# Group_04.net
KiCad netlist of a schematic drawn in EAGLE
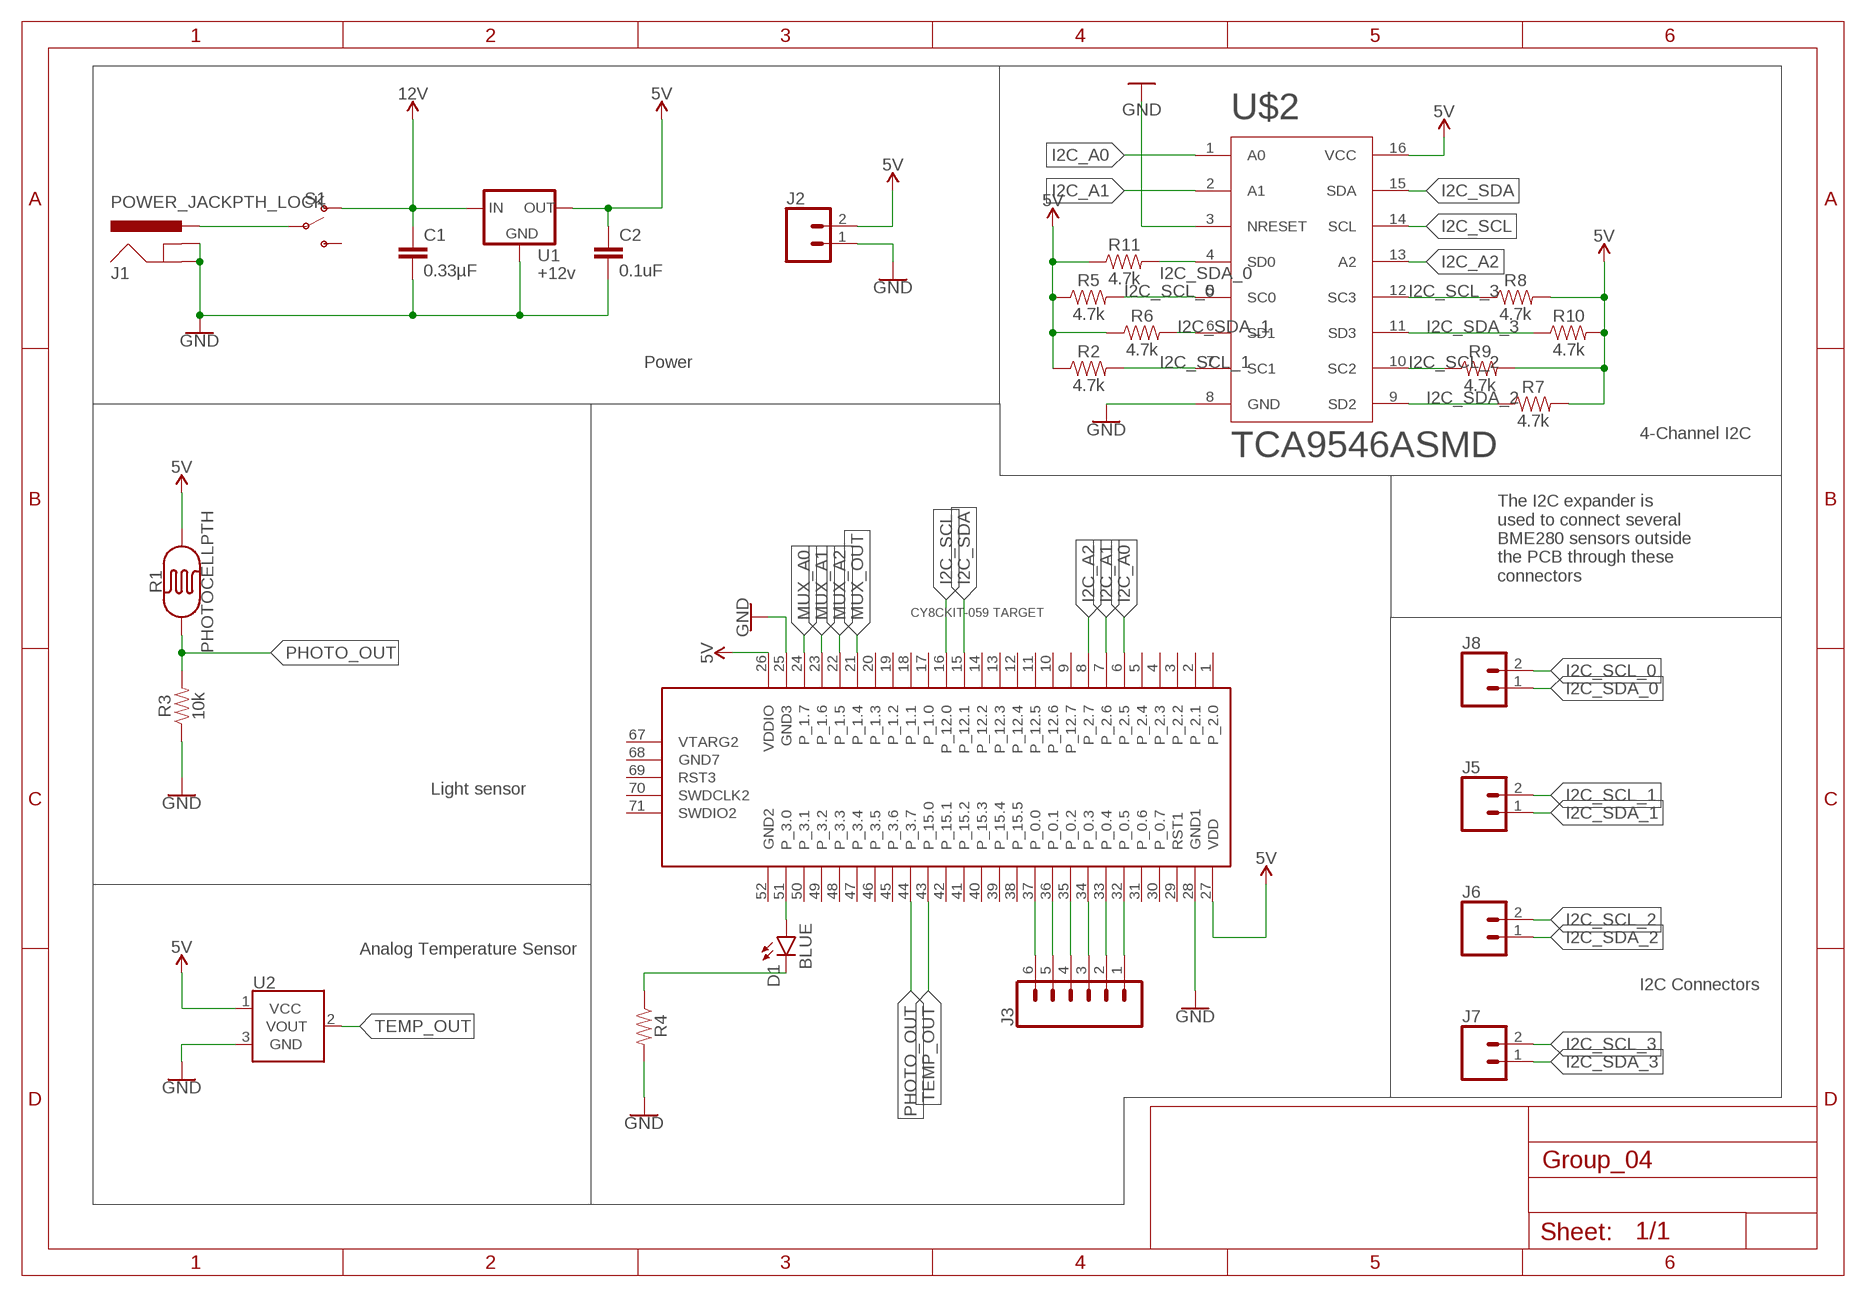
[diagram p0: schematic, sheet 1, part 1 of 2]
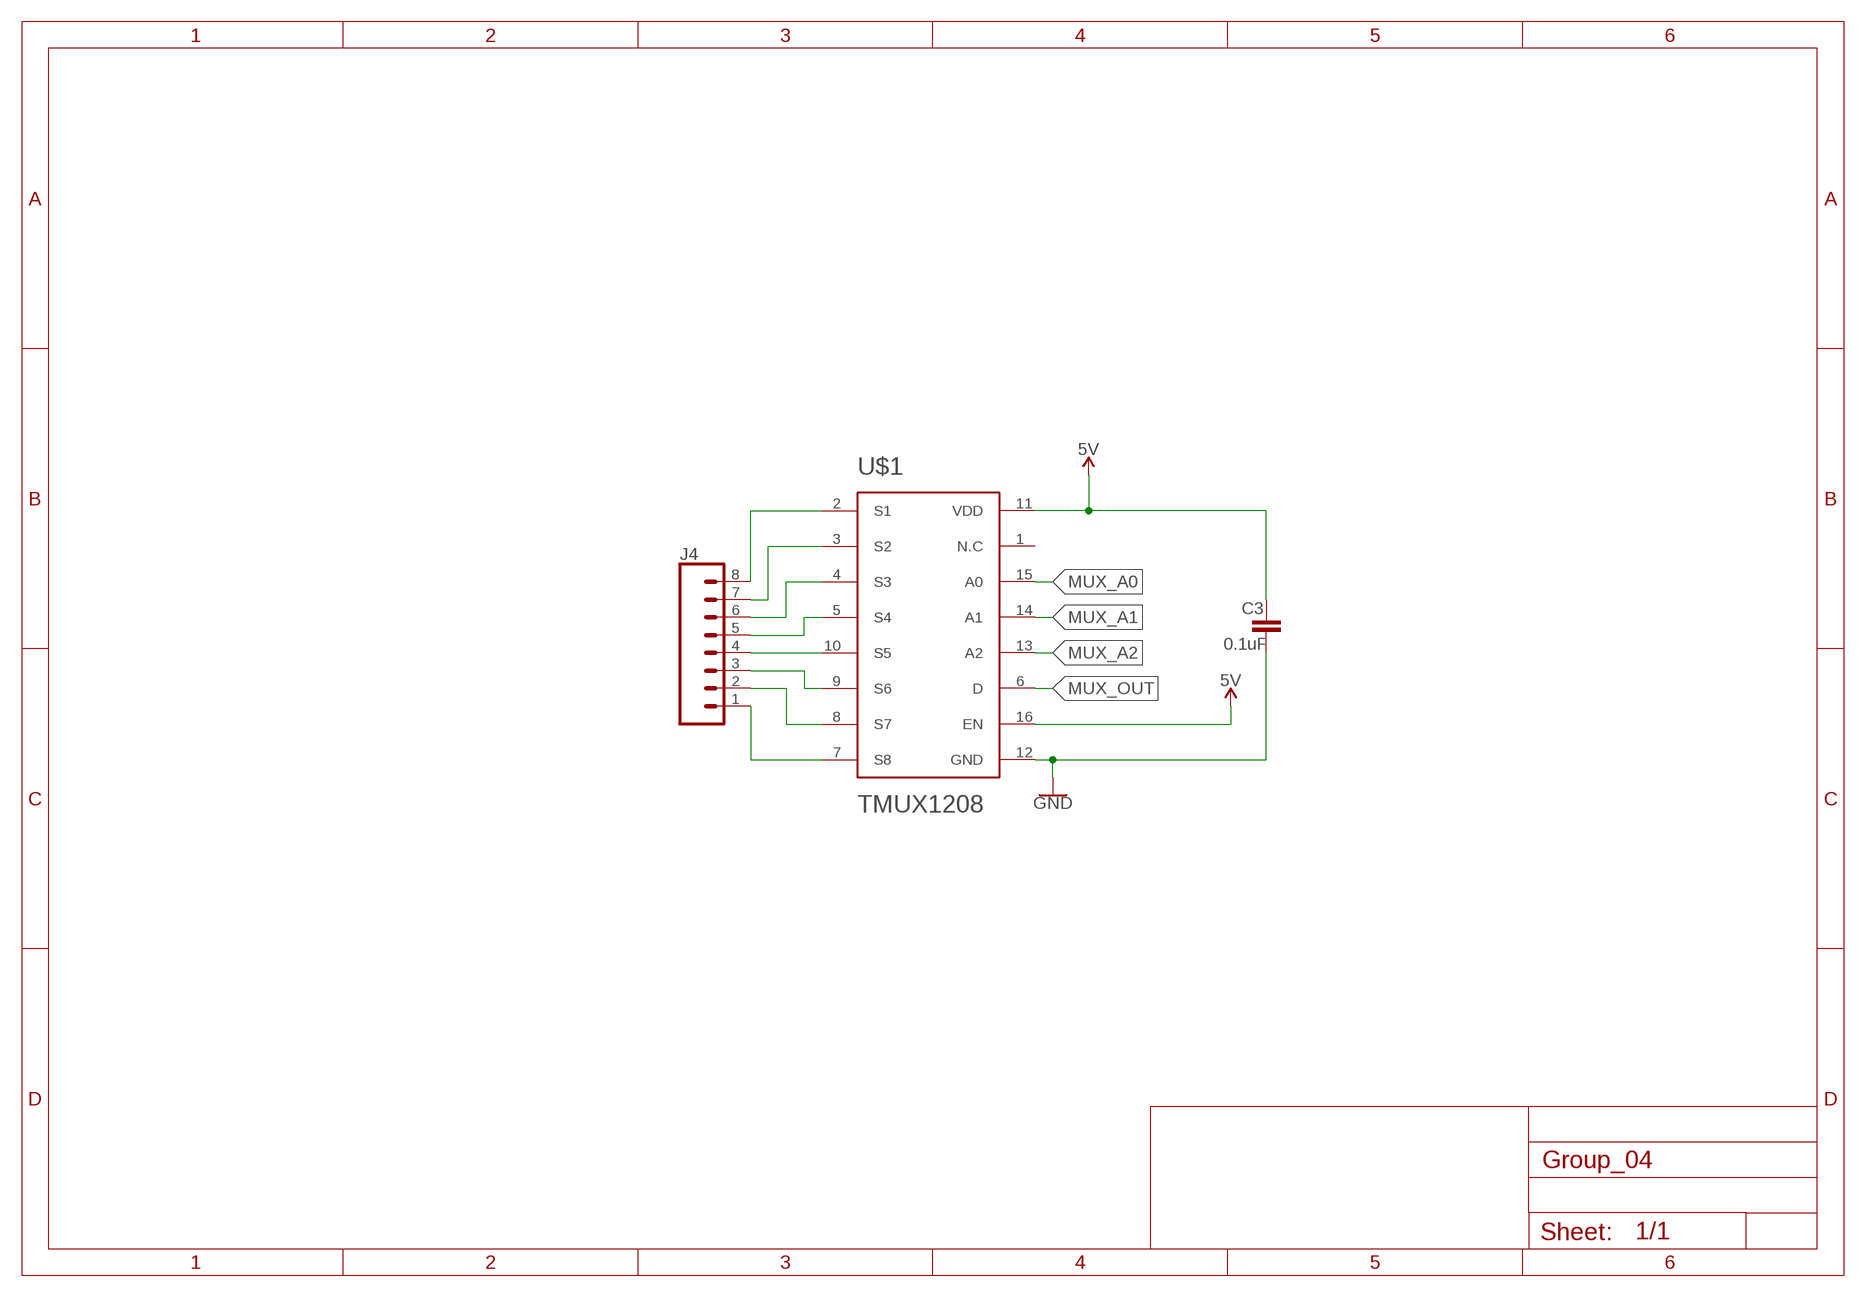
[diagram p1: schematic, sheet 1, part 2 of 2]

(export (version "E")
  (design (tool "Eeschema 10.0.6"))
  (components
    (comp (ref "C1")
      (value "0.33µF")
      (footprint "eagle-import:0805")
      (libsource (lib "eagle-import") (part "0.33UF/330NF-0805-50V-10%"))
    )
    (comp (ref "C2")
      (value "0.1uF")
      (footprint "eagle-import:CAP-PTH-SMALL-KIT")
      (libsource (lib "eagle-import") (part "0.1UF-KIT-EZ-50V-20%"))
    )
    (comp (ref "C3")
      (value "0.1uF")
      (footprint "eagle-import:CAP-PTH-SMALL-KIT")
      (libsource (lib "eagle-import") (part "0.1UF-KIT-EZ-50V-20%"))
    )
    (comp (ref "D1")
      (value "BLUE")
      (footprint "eagle-import:LED-1206")
      (libsource (lib "eagle-import") (part "LED-BLUE1206"))
    )
    (comp (ref "J1")
      (value "POWER_JACKPTH_LOCK")
      (footprint "eagle-import:POWER_JACK_PTH_LOCK")
      (libsource (lib "eagle-import") (part "POWER_JACKPTH_LOCK"))
    )
    (comp (ref "J2")
      (value "CONN_02")
      (footprint "eagle-import:1X02")
      (libsource (lib "eagle-import") (part "CONN_02"))
    )
    (comp (ref "J3")
      (value "CONN_06LOCK")
      (footprint "eagle-import:1X06_LOCK")
      (libsource (lib "eagle-import") (part "CONN_06LOCK"))
    )
    (comp (ref "J4")
      (value "CONN_08LOCK")
      (footprint "eagle-import:1X08_LOCK")
      (libsource (lib "eagle-import") (part "CONN_08LOCK"))
    )
    (comp (ref "J5")
      (value "CONN_02")
      (footprint "eagle-import:1X02")
      (libsource (lib "eagle-import") (part "CONN_02"))
    )
    (comp (ref "J6")
      (value "CONN_02")
      (footprint "eagle-import:1X02")
      (libsource (lib "eagle-import") (part "CONN_02"))
    )
    (comp (ref "J7")
      (value "CONN_02")
      (footprint "eagle-import:1X02")
      (libsource (lib "eagle-import") (part "CONN_02"))
    )
    (comp (ref "J8")
      (value "CONN_02")
      (footprint "eagle-import:1X02")
      (libsource (lib "eagle-import") (part "CONN_02"))
    )
    (comp (ref "R1")
      (value "PHOTOCELLPTH")
      (footprint "eagle-import:PHOTOCELL")
      (libsource (lib "eagle-import") (part "PHOTOCELLPTH"))
    )
    (comp (ref "R2")
      (value "4.7k")
      (footprint "eagle-import:0603")
      (libsource (lib "eagle-import") (part "4.7KOHM-0603-1/10W-1%"))
    )
    (comp (ref "R3")
      (value "10k")
      (footprint "eagle-import:0603")
      (libsource (lib "eagle-import") (part "10KOHM-0603-1/10W-1%"))
    )
    (comp (ref "R4")
      (value "RESISTORAXIAL-0.3")
      (footprint "eagle-import:AXIAL-0.3")
      (libsource (lib "eagle-import") (part "RESISTORAXIAL-0.3"))
    )
    (comp (ref "R5")
      (value "4.7k")
      (footprint "eagle-import:0603")
      (libsource (lib "eagle-import") (part "4.7KOHM-0603-1/10W-1%"))
    )
    (comp (ref "R6")
      (value "4.7k")
      (footprint "eagle-import:0603")
      (libsource (lib "eagle-import") (part "4.7KOHM-0603-1/10W-1%"))
    )
    (comp (ref "R7")
      (value "4.7k")
      (footprint "eagle-import:0603")
      (libsource (lib "eagle-import") (part "4.7KOHM-0603-1/10W-1%"))
    )
    (comp (ref "R8")
      (value "4.7k")
      (footprint "eagle-import:0603")
      (libsource (lib "eagle-import") (part "4.7KOHM-0603-1/10W-1%"))
    )
    (comp (ref "R9")
      (value "4.7k")
      (footprint "eagle-import:0603")
      (libsource (lib "eagle-import") (part "4.7KOHM-0603-1/10W-1%"))
    )
    (comp (ref "R10")
      (value "4.7k")
      (footprint "eagle-import:0603")
      (libsource (lib "eagle-import") (part "4.7KOHM-0603-1/10W-1%"))
    )
    (comp (ref "R11")
      (value "4.7k")
      (footprint "eagle-import:0603")
      (libsource (lib "eagle-import") (part "4.7KOHM-0603-1/10W-1%"))
    )
    (comp (ref "S1")
      (value "SWITCH-SPDT-PTH-11.6X4.0MM")
      (footprint "eagle-import:SWITCH_SPDT_PTH_11.6X4.0MM")
      (libsource (lib "eagle-import") (part "SWITCH-SPDT-PTH-11.6X4.0MM"))
    )
    (comp (ref "U$1")
      (value "TMUX1208")
      (footprint "eagle-import:QFN-16")
      (libsource (lib "eagle-import") (part "TMUX1208"))
    )
    (comp (ref "U$2")
      (value "TCA9546ASMD")
      (footprint "eagle-import:TSSOP-16")
      (libsource (lib "eagle-import") (part "TCA9546ASMD"))
    )
    (comp (ref "U$3")
      (value "CY8CKIT-059_TARGET")
      (footprint "eagle-import:CY8CKIT-059_TARGET")
      (libsource (lib "eagle-import") (part "CY8CKIT-059_TARGET"))
    )
    (comp (ref "U1")
      (value "+12v")
      (footprint "eagle-import:TO-252")
      (libsource (lib "eagle-import") (part "V_REG_78XX7812"))
    )
    (comp (ref "U2")
      (value "TMP36GT9")
      (footprint "eagle-import:TO-92")
      (libsource (lib "eagle-import") (part "TMP36GT9"))
    )
  )
  (nets
    (net (code "1") (name "5V") (class "Default")
      (node (ref "C2") (pin "1") (pinfunction "1_1") (pintype "passive"))
      (node (ref "C3") (pin "1") (pinfunction "1_1") (pintype "passive"))
      (node (ref "J2") (pin "2") (pinfunction "2_2") (pintype "passive"))
      (node (ref "R1") (pin "2") (pinfunction "P$2_2") (pintype "bidirectional"))
      (node (ref "R10") (pin "2") (pinfunction "2_2") (pintype "passive"))
      (node (ref "R11") (pin "1") (pinfunction "1_1") (pintype "passive"))
      (node (ref "R2") (pin "1") (pinfunction "1_1") (pintype "passive"))
      (node (ref "R5") (pin "1") (pinfunction "1_1") (pintype "passive"))
      (node (ref "R6") (pin "1") (pinfunction "1_1") (pintype "passive"))
      (node (ref "R7") (pin "2") (pinfunction "2_2") (pintype "passive"))
      (node (ref "R8") (pin "2") (pinfunction "2_2") (pintype "passive"))
      (node (ref "R9") (pin "2") (pinfunction "2_2") (pintype "passive"))
      (node (ref "U$1") (pin "11") (pinfunction "VDD_11") (pintype "bidirectional"))
      (node (ref "U$1") (pin "16") (pinfunction "EN_16") (pintype "bidirectional"))
      (node (ref "U$2") (pin "16") (pinfunction "VCC_16") (pintype "bidirectional"))
      (node (ref "U$3") (pin "26") (pinfunction "VDDIO_26") (pintype "bidirectional"))
      (node (ref "U$3") (pin "27") (pinfunction "VDD_27") (pintype "bidirectional"))
      (node (ref "U1") (pin "2") (pinfunction "OUT_2") (pintype "passive"))
      (node (ref "U2") (pin "1") (pinfunction "VCC_1") (pintype "bidirectional"))
    )
    (net (code "2") (name "12V") (class "Default")
      (node (ref "C1") (pin "1") (pinfunction "1_1") (pintype "passive"))
      (node (ref "S1") (pin "1") (pinfunction "O_1") (pintype "passive"))
      (node (ref "U1") (pin "1") (pinfunction "IN_1") (pintype "input"))
    )
    (net (code "3") (name "GND") (class "Default")
      (node (ref "C1") (pin "2") (pinfunction "2_2") (pintype "passive"))
      (node (ref "C2") (pin "2") (pinfunction "2_2") (pintype "passive"))
      (node (ref "C3") (pin "2") (pinfunction "2_2") (pintype "passive"))
      (node (ref "J1") (pin "GND") (pinfunction "GND_GND") (pintype "bidirectional"))
      (node (ref "J1") (pin "GNDBREAK") (pinfunction "GNDBREAK_GNDBREAK") (pintype "bidirectional"))
      (node (ref "J2") (pin "1") (pinfunction "1_1") (pintype "passive"))
      (node (ref "R3") (pin "1") (pinfunction "1_1") (pintype "passive"))
      (node (ref "R4") (pin "P$2") (pinfunction "2_P$2") (pintype "passive"))
      (node (ref "U$1") (pin "12") (pinfunction "GND_12") (pintype "bidirectional"))
      (node (ref "U$2") (pin "3") (pinfunction "NRESET_3") (pintype "bidirectional"))
      (node (ref "U$2") (pin "8") (pinfunction "GND_8") (pintype "bidirectional"))
      (node (ref "U$3") (pin "25") (pinfunction "GND3_25") (pintype "bidirectional"))
      (node (ref "U$3") (pin "28") (pinfunction "GND1_28") (pintype "bidirectional"))
      (node (ref "U1") (pin "3") (pinfunction "GND_3") (pintype "input"))
      (node (ref "U2") (pin "3") (pinfunction "GND_3") (pintype "bidirectional"))
    )
    (net (code "4") (name "I2C_A0") (class "Default")
      (node (ref "U$2") (pin "1") (pinfunction "A0_1") (pintype "bidirectional"))
      (node (ref "U$3") (pin "6") (pinfunction "P_2.5_6") (pintype "bidirectional"))
    )
    (net (code "5") (name "I2C_A1") (class "Default")
      (node (ref "U$2") (pin "2") (pinfunction "A1_2") (pintype "bidirectional"))
      (node (ref "U$3") (pin "7") (pinfunction "P_2.6_7") (pintype "bidirectional"))
    )
    (net (code "6") (name "I2C_A2") (class "Default")
      (node (ref "U$2") (pin "13") (pinfunction "A2_13") (pintype "bidirectional"))
      (node (ref "U$3") (pin "8") (pinfunction "P_2.7_8") (pintype "bidirectional"))
    )
    (net (code "7") (name "I2C_SCL") (class "Default")
      (node (ref "U$2") (pin "14") (pinfunction "SCL_14") (pintype "bidirectional"))
      (node (ref "U$3") (pin "16") (pinfunction "P_12.0_16") (pintype "bidirectional"))
    )
    (net (code "8") (name "I2C_SCL_0") (class "Default")
      (node (ref "J8") (pin "2") (pinfunction "2_2") (pintype "passive"))
      (node (ref "R5") (pin "2") (pinfunction "2_2") (pintype "passive"))
      (node (ref "U$2") (pin "5") (pinfunction "SC0_5") (pintype "bidirectional"))
    )
    (net (code "9") (name "I2C_SCL_1") (class "Default")
      (node (ref "J5") (pin "2") (pinfunction "2_2") (pintype "passive"))
      (node (ref "R2") (pin "2") (pinfunction "2_2") (pintype "passive"))
      (node (ref "U$2") (pin "7") (pinfunction "SC1_7") (pintype "bidirectional"))
    )
    (net (code "10") (name "I2C_SCL_2") (class "Default")
      (node (ref "J6") (pin "2") (pinfunction "2_2") (pintype "passive"))
      (node (ref "R9") (pin "1") (pinfunction "1_1") (pintype "passive"))
      (node (ref "U$2") (pin "10") (pinfunction "SC2_10") (pintype "bidirectional"))
    )
    (net (code "11") (name "I2C_SCL_3") (class "Default")
      (node (ref "J7") (pin "2") (pinfunction "2_2") (pintype "passive"))
      (node (ref "R8") (pin "1") (pinfunction "1_1") (pintype "passive"))
      (node (ref "U$2") (pin "12") (pinfunction "SC3_12") (pintype "bidirectional"))
    )
    (net (code "12") (name "I2C_SDA") (class "Default")
      (node (ref "U$2") (pin "15") (pinfunction "SDA_15") (pintype "bidirectional"))
      (node (ref "U$3") (pin "15") (pinfunction "P_12.1_15") (pintype "bidirectional"))
    )
    (net (code "13") (name "I2C_SDA_0") (class "Default")
      (node (ref "J8") (pin "1") (pinfunction "1_1") (pintype "passive"))
      (node (ref "R11") (pin "2") (pinfunction "2_2") (pintype "passive"))
      (node (ref "U$2") (pin "4") (pinfunction "SD0_4") (pintype "bidirectional"))
    )
    (net (code "14") (name "I2C_SDA_1") (class "Default")
      (node (ref "J5") (pin "1") (pinfunction "1_1") (pintype "passive"))
      (node (ref "R6") (pin "2") (pinfunction "2_2") (pintype "passive"))
      (node (ref "U$2") (pin "6") (pinfunction "SD1_6") (pintype "bidirectional"))
    )
    (net (code "15") (name "I2C_SDA_2") (class "Default")
      (node (ref "J6") (pin "1") (pinfunction "1_1") (pintype "passive"))
      (node (ref "R7") (pin "1") (pinfunction "1_1") (pintype "passive"))
      (node (ref "U$2") (pin "9") (pinfunction "SD2_9") (pintype "bidirectional"))
    )
    (net (code "16") (name "I2C_SDA_3") (class "Default")
      (node (ref "J7") (pin "1") (pinfunction "1_1") (pintype "passive"))
      (node (ref "R10") (pin "1") (pinfunction "1_1") (pintype "passive"))
      (node (ref "U$2") (pin "11") (pinfunction "SD3_11") (pintype "bidirectional"))
    )
    (net (code "17") (name "MUX_A0") (class "Default")
      (node (ref "U$1") (pin "15") (pinfunction "A0_15") (pintype "bidirectional"))
      (node (ref "U$3") (pin "24") (pinfunction "P_1.7_24") (pintype "bidirectional"))
    )
    (net (code "18") (name "MUX_A1") (class "Default")
      (node (ref "U$1") (pin "14") (pinfunction "A1_14") (pintype "bidirectional"))
      (node (ref "U$3") (pin "23") (pinfunction "P_1.6_23") (pintype "bidirectional"))
    )
    (net (code "19") (name "MUX_A2") (class "Default")
      (node (ref "U$1") (pin "13") (pinfunction "A2_13") (pintype "bidirectional"))
      (node (ref "U$3") (pin "22") (pinfunction "P_1.5_22") (pintype "bidirectional"))
    )
    (net (code "20") (name "MUX_OUT") (class "Default")
      (node (ref "U$1") (pin "6") (pinfunction "D_6") (pintype "bidirectional"))
      (node (ref "U$3") (pin "21") (pinfunction "P_1.4_21") (pintype "bidirectional"))
    )
    (net (code "21") (name "Net-(R4-1)") (class "Default")
      (node (ref "D1") (pin "C") (pinfunction "C_C") (pintype "passive"))
      (node (ref "R4") (pin "P$1") (pinfunction "1_P$1") (pintype "passive"))
    )
    (net (code "22") (name "Net-(S1-P)") (class "Default")
      (node (ref "J1") (pin "PWR") (pinfunction "PWR_PWR") (pintype "bidirectional"))
      (node (ref "S1") (pin "2") (pinfunction "P_2") (pintype "passive"))
    )
    (net (code "23") (name "Net-(U$1-S1)") (class "Default")
      (node (ref "J4") (pin "8") (pinfunction "8_8") (pintype "passive"))
      (node (ref "U$1") (pin "2") (pinfunction "S1_2") (pintype "bidirectional"))
    )
    (net (code "24") (name "Net-(U$1-S2)") (class "Default")
      (node (ref "J4") (pin "7") (pinfunction "7_7") (pintype "passive"))
      (node (ref "U$1") (pin "3") (pinfunction "S2_3") (pintype "bidirectional"))
    )
    (net (code "25") (name "Net-(U$1-S3)") (class "Default")
      (node (ref "J4") (pin "6") (pinfunction "6_6") (pintype "passive"))
      (node (ref "U$1") (pin "4") (pinfunction "S3_4") (pintype "bidirectional"))
    )
    (net (code "26") (name "Net-(U$1-S4)") (class "Default")
      (node (ref "J4") (pin "5") (pinfunction "5_5") (pintype "passive"))
      (node (ref "U$1") (pin "5") (pinfunction "S4_5") (pintype "bidirectional"))
    )
    (net (code "27") (name "Net-(U$1-S5)") (class "Default")
      (node (ref "J4") (pin "4") (pinfunction "4_4") (pintype "passive"))
      (node (ref "U$1") (pin "10") (pinfunction "S5_10") (pintype "bidirectional"))
    )
    (net (code "28") (name "Net-(U$1-S6)") (class "Default")
      (node (ref "J4") (pin "3") (pinfunction "3_3") (pintype "passive"))
      (node (ref "U$1") (pin "9") (pinfunction "S6_9") (pintype "bidirectional"))
    )
    (net (code "29") (name "Net-(U$1-S7)") (class "Default")
      (node (ref "J4") (pin "2") (pinfunction "2_2") (pintype "passive"))
      (node (ref "U$1") (pin "8") (pinfunction "S7_8") (pintype "bidirectional"))
    )
    (net (code "30") (name "Net-(U$1-S8)") (class "Default")
      (node (ref "J4") (pin "1") (pinfunction "1_1") (pintype "passive"))
      (node (ref "U$1") (pin "7") (pinfunction "S8_7") (pintype "bidirectional"))
    )
    (net (code "31") (name "Net-(U$3-P_0.0)") (class "Default")
      (node (ref "J3") (pin "6") (pinfunction "6_6") (pintype "passive"))
      (node (ref "U$3") (pin "37") (pinfunction "P_0.0_37") (pintype "bidirectional"))
    )
    (net (code "32") (name "Net-(U$3-P_0.1)") (class "Default")
      (node (ref "J3") (pin "5") (pinfunction "5_5") (pintype "passive"))
      (node (ref "U$3") (pin "36") (pinfunction "P_0.1_36") (pintype "bidirectional"))
    )
    (net (code "33") (name "Net-(U$3-P_0.2)") (class "Default")
      (node (ref "J3") (pin "4") (pinfunction "4_4") (pintype "passive"))
      (node (ref "U$3") (pin "35") (pinfunction "P_0.2_35") (pintype "bidirectional"))
    )
    (net (code "34") (name "Net-(U$3-P_0.3)") (class "Default")
      (node (ref "J3") (pin "3") (pinfunction "3_3") (pintype "passive"))
      (node (ref "U$3") (pin "34") (pinfunction "P_0.3_34") (pintype "bidirectional"))
    )
    (net (code "35") (name "Net-(U$3-P_0.4)") (class "Default")
      (node (ref "J3") (pin "2") (pinfunction "2_2") (pintype "passive"))
      (node (ref "U$3") (pin "33") (pinfunction "P_0.4_33") (pintype "bidirectional"))
    )
    (net (code "36") (name "Net-(U$3-P_0.5)") (class "Default")
      (node (ref "J3") (pin "1") (pinfunction "1_1") (pintype "passive"))
      (node (ref "U$3") (pin "32") (pinfunction "P_0.5_32") (pintype "bidirectional"))
    )
    (net (code "37") (name "Net-(U$3-P_3.0)") (class "Default")
      (node (ref "D1") (pin "A") (pinfunction "A_A") (pintype "passive"))
      (node (ref "U$3") (pin "51") (pinfunction "P_3.0_51") (pintype "bidirectional"))
    )
    (net (code "38") (name "PHOTO_OUT") (class "Default")
      (node (ref "R1") (pin "1") (pinfunction "P$1_1") (pintype "bidirectional"))
      (node (ref "R3") (pin "2") (pinfunction "2_2") (pintype "passive"))
      (node (ref "U$3") (pin "44") (pinfunction "P_3.7_44") (pintype "bidirectional"))
    )
    (net (code "39") (name "TEMP_OUT") (class "Default")
      (node (ref "U$3") (pin "43") (pinfunction "P_15.0_43") (pintype "bidirectional"))
      (node (ref "U2") (pin "2") (pinfunction "VOUT_2") (pintype "bidirectional"))
    )
    (net (code "40") (name "unconnected-(S1-S-Pad3)") (class "Default")
      (node (ref "S1") (pin "3") (pinfunction "S_3") (pintype "passive"))
    )
    (net (code "41") (name "unconnected-(U$1-N.C-Pad1)") (class "Default")
      (node (ref "U$1") (pin "1") (pinfunction "N.C_1") (pintype "bidirectional"))
    )
    (net (code "42") (name "unconnected-(U$3-GND2-Pad52)") (class "Default")
      (node (ref "U$3") (pin "52") (pinfunction "GND2_52") (pintype "bidirectional"))
    )
    (net (code "43") (name "unconnected-(U$3-GND7-Pad68)") (class "Default")
      (node (ref "U$3") (pin "68") (pinfunction "GND7_68") (pintype "bidirectional"))
    )
    (net (code "44") (name "unconnected-(U$3-P_0.6-Pad31)") (class "Default")
      (node (ref "U$3") (pin "31") (pinfunction "P_0.6_31") (pintype "bidirectional"))
    )
    (net (code "45") (name "unconnected-(U$3-P_0.7-Pad30)") (class "Default")
      (node (ref "U$3") (pin "30") (pinfunction "P_0.7_30") (pintype "bidirectional"))
    )
    (net (code "46") (name "unconnected-(U$3-P_1.0-Pad17)") (class "Default")
      (node (ref "U$3") (pin "17") (pinfunction "P_1.0_17") (pintype "bidirectional"))
    )
    (net (code "47") (name "unconnected-(U$3-P_1.1-Pad18)") (class "Default")
      (node (ref "U$3") (pin "18") (pinfunction "P_1.1_18") (pintype "bidirectional"))
    )
    (net (code "48") (name "unconnected-(U$3-P_1.2-Pad19)") (class "Default")
      (node (ref "U$3") (pin "19") (pinfunction "P_1.2_19") (pintype "bidirectional"))
    )
    (net (code "49") (name "unconnected-(U$3-P_1.3-Pad20)") (class "Default")
      (node (ref "U$3") (pin "20") (pinfunction "P_1.3_20") (pintype "bidirectional"))
    )
    (net (code "50") (name "unconnected-(U$3-P_2.0-Pad1)") (class "Default")
      (node (ref "U$3") (pin "1") (pinfunction "P_2.0_1") (pintype "bidirectional"))
    )
    (net (code "51") (name "unconnected-(U$3-P_2.1-Pad2)") (class "Default")
      (node (ref "U$3") (pin "2") (pinfunction "P_2.1_2") (pintype "bidirectional"))
    )
    (net (code "52") (name "unconnected-(U$3-P_2.2-Pad3)") (class "Default")
      (node (ref "U$3") (pin "3") (pinfunction "P_2.2_3") (pintype "bidirectional"))
    )
    (net (code "53") (name "unconnected-(U$3-P_2.3-Pad4)") (class "Default")
      (node (ref "U$3") (pin "4") (pinfunction "P_2.3_4") (pintype "bidirectional"))
    )
    (net (code "54") (name "unconnected-(U$3-P_2.4-Pad5)") (class "Default")
      (node (ref "U$3") (pin "5") (pinfunction "P_2.4_5") (pintype "bidirectional"))
    )
    (net (code "55") (name "unconnected-(U$3-P_3.1-Pad50)") (class "Default")
      (node (ref "U$3") (pin "50") (pinfunction "P_3.1_50") (pintype "bidirectional"))
    )
    (net (code "56") (name "unconnected-(U$3-P_3.2-Pad49)") (class "Default")
      (node (ref "U$3") (pin "49") (pinfunction "P_3.2_49") (pintype "bidirectional"))
    )
    (net (code "57") (name "unconnected-(U$3-P_3.3-Pad48)") (class "Default")
      (node (ref "U$3") (pin "48") (pinfunction "P_3.3_48") (pintype "bidirectional"))
    )
    (net (code "58") (name "unconnected-(U$3-P_3.4-Pad47)") (class "Default")
      (node (ref "U$3") (pin "47") (pinfunction "P_3.4_47") (pintype "bidirectional"))
    )
    (net (code "59") (name "unconnected-(U$3-P_3.5-Pad46)") (class "Default")
      (node (ref "U$3") (pin "46") (pinfunction "P_3.5_46") (pintype "bidirectional"))
    )
    (net (code "60") (name "unconnected-(U$3-P_3.6-Pad45)") (class "Default")
      (node (ref "U$3") (pin "45") (pinfunction "P_3.6_45") (pintype "bidirectional"))
    )
    (net (code "61") (name "unconnected-(U$3-P_12.2-Pad14)") (class "Default")
      (node (ref "U$3") (pin "14") (pinfunction "P_12.2_14") (pintype "bidirectional"))
    )
    (net (code "62") (name "unconnected-(U$3-P_12.3-Pad13)") (class "Default")
      (node (ref "U$3") (pin "13") (pinfunction "P_12.3_13") (pintype "bidirectional"))
    )
    (net (code "63") (name "unconnected-(U$3-P_12.4-Pad12)") (class "Default")
      (node (ref "U$3") (pin "12") (pinfunction "P_12.4_12") (pintype "bidirectional"))
    )
    (net (code "64") (name "unconnected-(U$3-P_12.5-Pad11)") (class "Default")
      (node (ref "U$3") (pin "11") (pinfunction "P_12.5_11") (pintype "bidirectional"))
    )
    (net (code "65") (name "unconnected-(U$3-P_12.6-Pad10)") (class "Default")
      (node (ref "U$3") (pin "10") (pinfunction "P_12.6_10") (pintype "bidirectional"))
    )
    (net (code "66") (name "unconnected-(U$3-P_12.7-Pad9)") (class "Default")
      (node (ref "U$3") (pin "9") (pinfunction "P_12.7_9") (pintype "bidirectional"))
    )
    (net (code "67") (name "unconnected-(U$3-P_15.1-Pad42)") (class "Default")
      (node (ref "U$3") (pin "42") (pinfunction "P_15.1_42") (pintype "bidirectional"))
    )
    (net (code "68") (name "unconnected-(U$3-P_15.2-Pad41)") (class "Default")
      (node (ref "U$3") (pin "41") (pinfunction "P_15.2_41") (pintype "bidirectional"))
    )
    (net (code "69") (name "unconnected-(U$3-P_15.3-Pad40)") (class "Default")
      (node (ref "U$3") (pin "40") (pinfunction "P_15.3_40") (pintype "bidirectional"))
    )
    (net (code "70") (name "unconnected-(U$3-P_15.4-Pad39)") (class "Default")
      (node (ref "U$3") (pin "39") (pinfunction "P_15.4_39") (pintype "bidirectional"))
    )
    (net (code "71") (name "unconnected-(U$3-P_15.5-Pad38)") (class "Default")
      (node (ref "U$3") (pin "38") (pinfunction "P_15.5_38") (pintype "bidirectional"))
    )
    (net (code "72") (name "unconnected-(U$3-RST1-Pad29)") (class "Default")
      (node (ref "U$3") (pin "29") (pinfunction "RST1_29") (pintype "bidirectional"))
    )
    (net (code "73") (name "unconnected-(U$3-RST3-Pad69)") (class "Default")
      (node (ref "U$3") (pin "69") (pinfunction "RST3_69") (pintype "bidirectional"))
    )
    (net (code "74") (name "unconnected-(U$3-SWDCLK2-Pad70)") (class "Default")
      (node (ref "U$3") (pin "70") (pinfunction "SWDCLK2_70") (pintype "bidirectional"))
    )
    (net (code "75") (name "unconnected-(U$3-SWDIO2-Pad71)") (class "Default")
      (node (ref "U$3") (pin "71") (pinfunction "SWDIO2_71") (pintype "bidirectional"))
    )
    (net (code "76") (name "unconnected-(U$3-VTARG2-Pad67)") (class "Default")
      (node (ref "U$3") (pin "67") (pinfunction "VTARG2_67") (pintype "bidirectional"))
    )
  )
)
